# AnalogHmwsch.net
KiCad netlist of a schematic drawn in Altium Designer
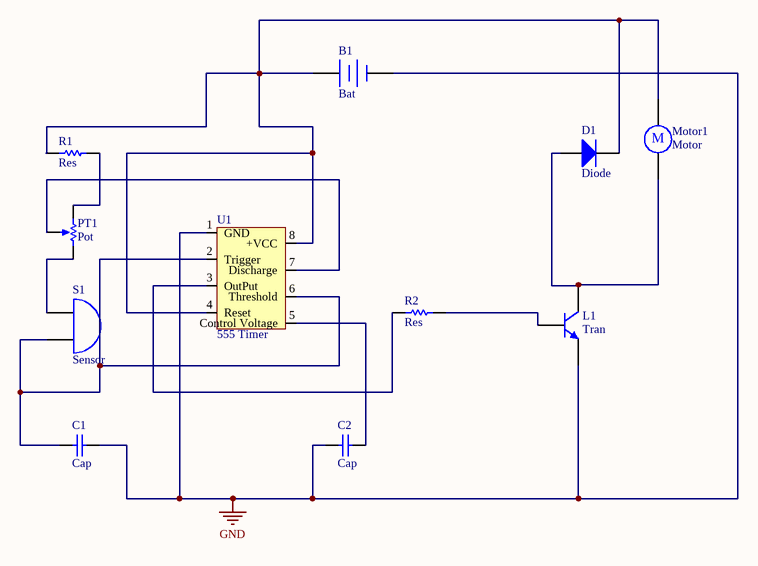
[diagram p0: AnalogHmwsch.SchDoc]

(export (version "E")
  (design (tool "Eeschema 10.0.6"))
  (components
    (comp (ref "B1") (value "Bat") (footprint "Bat") (libsource (lib "AnalogHmwschlib") (part "Bat")))
    (comp (ref "C1") (value "Cap") (footprint "Cap") (libsource (lib "AnalogHmwschlib") (part "Cap")))
    (comp (ref "C2") (value "Cap") (footprint "Cap") (libsource (lib "AnalogHmwschlib") (part "Cap")))
    (comp (ref "D1") (value "Diode") (footprint "Diode") (libsource (lib "AnalogHmwschlib") (part "Diode")))
    (comp (ref "L1") (value "Tran") (footprint "Tran") (libsource (lib "AnalogHmwschlib") (part "Tran")))
    (comp (ref "Motor1")
      (value "Motor")
      (footprint "Motor")
      (libsource (lib "AnalogHmwschlib") (part "Motor"))
    )
    (comp (ref "PT1") (value "Pot") (footprint "Pot") (libsource (lib "AnalogHmwschlib") (part "Pot")))
    (comp (ref "R1") (value "Res") (footprint "Res") (libsource (lib "AnalogHmwschlib") (part "Res")))
    (comp (ref "R2") (value "Res") (footprint "Res") (libsource (lib "AnalogHmwschlib") (part "Res")))
    (comp (ref "S1")
      (value "Sensor")
      (footprint "Sensor")
      (libsource (lib "AnalogHmwschlib") (part "Sensor"))
    )
    (comp (ref "U1")
      (value "555 Timer")
      (footprint "555 Timer")
      (libsource (lib "AnalogHmwschlib") (part "555 Timer"))
    )
  )
  (nets
    (net (code "1") (name "GND") (class "Default")
      (node (ref "B1") (pin "2") (pinfunction "-_2") (pintype "passive"))
      (node (ref "C1") (pin "2") (pinfunction "2_2") (pintype "passive"))
      (node (ref "C2") (pin "1") (pinfunction "1_1") (pintype "passive"))
      (node (ref "L1") (pin "3") (pinfunction "E_3") (pintype "passive"))
      (node (ref "U1") (pin "1") (pinfunction "GND_1") (pintype "passive"))
    )
    (net (code "2") (name "Net-(B1-+)") (class "Default")
      (node (ref "B1") (pin "1") (pinfunction "+_1") (pintype "passive"))
      (node (ref "D1") (pin "2") (pinfunction "K_2") (pintype "passive"))
      (node (ref "Motor1") (pin "1") (pinfunction "1_1") (pintype "passive"))
      (node (ref "R1") (pin "1") (pinfunction "1_1") (pintype "passive"))
      (node (ref "U1") (pin "4") (pinfunction "Reset_4") (pintype "passive"))
      (node (ref "U1") (pin "8") (pinfunction "+VCC_8") (pintype "passive"))
    )
    (net (code "3") (name "Net-(D1-A)") (class "Default")
      (node (ref "D1") (pin "1") (pinfunction "A_1") (pintype "passive"))
      (node (ref "L1") (pin "1") (pinfunction "C_1") (pintype "passive"))
      (node (ref "Motor1") (pin "2") (pinfunction "2_2") (pintype "passive"))
    )
    (net (code "4") (name "Net-(L1-B)") (class "Default")
      (node (ref "L1") (pin "2") (pinfunction "B_2") (pintype "passive"))
      (node (ref "R2") (pin "2") (pinfunction "2_2") (pintype "passive"))
    )
    (net (code "5") (name "Net-(PT1-BOT)") (class "Default")
      (node (ref "PT1") (pin "2") (pinfunction "BOT_2") (pintype "passive"))
      (node (ref "S1") (pin "1") (pinfunction "A_1") (pintype "passive"))
    )
    (net (code "6") (name "Net-(PT1-TAP)") (class "Default")
      (node (ref "PT1") (pin "3") (pinfunction "TAP_3") (pintype "passive"))
      (node (ref "U1") (pin "7") (pinfunction "Discharge_7") (pintype "passive"))
    )
    (net (code "7") (name "Net-(PT1-TOP)") (class "Default")
      (node (ref "PT1") (pin "1") (pinfunction "TOP_1") (pintype "passive"))
      (node (ref "R1") (pin "2") (pinfunction "2_2") (pintype "passive"))
    )
    (net (code "8") (name "Net-(S1-B)") (class "Default")
      (node (ref "C1") (pin "1") (pinfunction "1_1") (pintype "passive"))
      (node (ref "S1") (pin "2") (pinfunction "B_2") (pintype "passive"))
      (node (ref "U1") (pin "2") (pinfunction "Trigger_2") (pintype "passive"))
      (node (ref "U1") (pin "6") (pinfunction "Threshold_6") (pintype "passive"))
    )
    (net (code "9") (name "Net-(U1-Control_Voltage)") (class "Default")
      (node (ref "C2") (pin "2") (pinfunction "2_2") (pintype "passive"))
      (node (ref "U1") (pin "5") (pinfunction "Control_Voltage_5") (pintype "passive"))
    )
    (net (code "10") (name "Net-(U1-OutPut)") (class "Default")
      (node (ref "R2") (pin "1") (pinfunction "1_1") (pintype "passive"))
      (node (ref "U1") (pin "3") (pinfunction "OutPut_3") (pintype "passive"))
    )
  )
)
